# power.net
KiCad netlist of a schematic drawn in Altium Designer
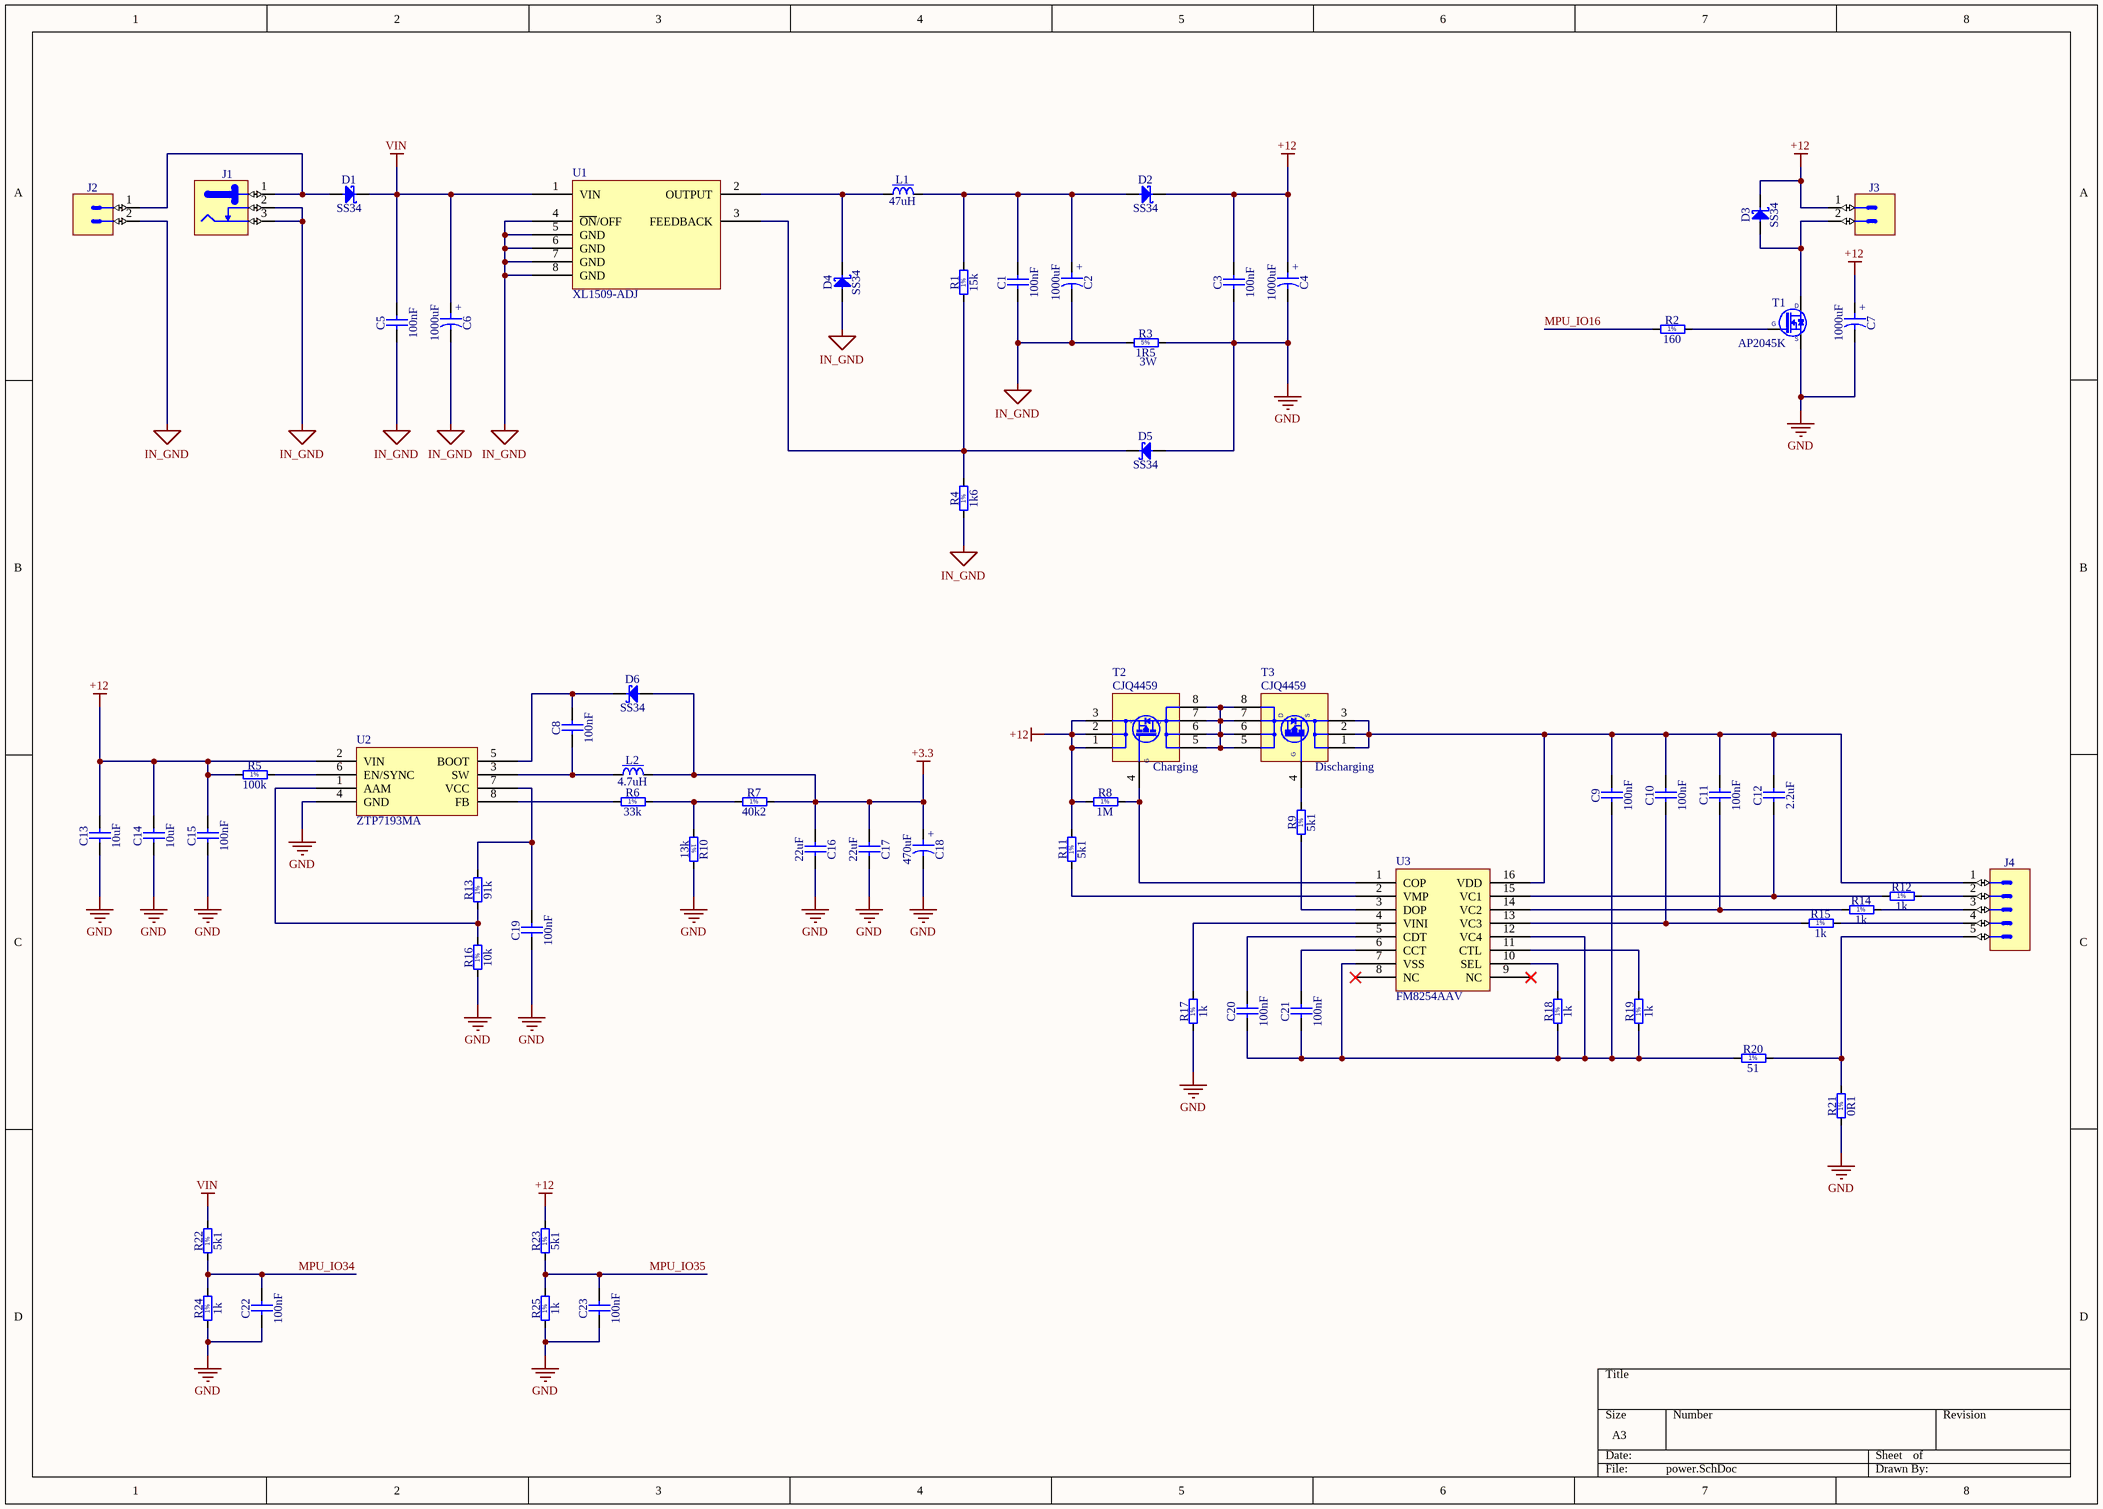
[diagram p0: power.SchDoc]

(export (version "E")
  (design (tool "Eeschema 10.0.6"))
  (components
    (comp (ref "C1")
      (value "100nF")
      (footprint "CAPC2012X135N")
      (description "Non-polarised capacitor")
      (fields
        (field (name "PART NUMBER") "CC0805_100NF_50V_10%_X7R")
        (field (name "VOLTAGE") "50V")
        (field (name "AUTHOR") "CERN DEM JLC")
      )
      (libsource (lib "Capacitors") (part "Capacitor - non polarized"))
    )
    (comp (ref "C2")
      (value "1000uF")
      (footprint "CAPPR500-1300X2200")
      (description "Polarised capacitor")
      (fields
        (field (name "PART NUMBER") "CAER_1000UF_25V_20%_RUBYCON_ZL")
        (field (name "VOLTAGE") "25V")
        (field (name "AUTHOR") "CERN DEM JLC")
      )
      (libsource (lib "Capacitors") (part "Capacitor - polarized"))
    )
    (comp (ref "C3")
      (value "100nF")
      (footprint "CAPC2012X135N")
      (description "Non-polarised capacitor")
      (fields
        (field (name "PART NUMBER") "CC0805_100NF_50V_10%_X7R")
        (field (name "VOLTAGE") "50V")
        (field (name "AUTHOR") "CERN DEM JLC")
      )
      (libsource (lib "Capacitors") (part "Capacitor - non polarized"))
    )
    (comp (ref "C4")
      (value "1000uF")
      (footprint "CAPPR500-1300X2200")
      (description "Polarised capacitor")
      (fields
        (field (name "PART NUMBER") "CAER_1000UF_25V_20%_RUBYCON_ZL")
        (field (name "VOLTAGE") "25V")
        (field (name "AUTHOR") "CERN DEM JLC")
      )
      (libsource (lib "Capacitors") (part "Capacitor - polarized"))
    )
    (comp (ref "C5")
      (value "100nF")
      (footprint "CAPC2012X135N")
      (description "Non-polarised capacitor")
      (fields
        (field (name "PART NUMBER") "CC0805_100NF_50V_10%_X7R")
        (field (name "VOLTAGE") "50V")
        (field (name "AUTHOR") "CERN DEM JLC")
      )
      (libsource (lib "Capacitors") (part "Capacitor - non polarized"))
    )
    (comp (ref "C6")
      (value "1000uF")
      (footprint "CAPPR500-1300X2200")
      (description "Polarised capacitor")
      (fields
        (field (name "PART NUMBER") "CAER_1000UF_25V_20%_RUBYCON_ZL")
        (field (name "VOLTAGE") "25V")
        (field (name "AUTHOR") "CERN DEM JLC")
      )
      (libsource (lib "Capacitors") (part "Capacitor - polarized"))
    )
    (comp (ref "C7")
      (value "1000uF")
      (footprint "CAPPR500-1300X2200")
      (description "Polarised capacitor")
      (fields
        (field (name "PART NUMBER") "CAER_1000UF_25V_20%_RUBYCON_ZL")
        (field (name "VOLTAGE") "25V")
        (field (name "AUTHOR") "CERN DEM JLC")
      )
      (libsource (lib "Capacitors") (part "Capacitor - polarized"))
    )
    (comp (ref "C8")
      (value "100nF")
      (footprint "CAPC2012X135N")
      (description "Non-polarised capacitor")
      (fields
        (field (name "PART NUMBER") "CC0805_100NF_50V_10%_X7R")
        (field (name "VOLTAGE") "50V")
        (field (name "AUTHOR") "CERN DEM JLC")
      )
      (libsource (lib "Capacitors") (part "Capacitor - non polarized"))
    )
    (comp (ref "C9")
      (value "100nF")
      (footprint "CAPC2012X135N")
      (description "Non-polarised capacitor")
      (fields
        (field (name "PART NUMBER") "CC0805_100NF_50V_10%_X7R")
        (field (name "VOLTAGE") "50V")
        (field (name "AUTHOR") "CERN DEM JLC")
      )
      (libsource (lib "Capacitors") (part "Capacitor - non polarized"))
    )
    (comp (ref "C10")
      (value "100nF")
      (footprint "CAPC2012X135N")
      (description "Non-polarised capacitor")
      (fields
        (field (name "PART NUMBER") "CC0805_100NF_50V_10%_X7R")
        (field (name "VOLTAGE") "50V")
        (field (name "AUTHOR") "CERN DEM JLC")
      )
      (libsource (lib "Capacitors") (part "Capacitor - non polarized"))
    )
    (comp (ref "C11")
      (value "100nF")
      (footprint "CAPC2012X135N")
      (description "Non-polarised capacitor")
      (fields
        (field (name "PART NUMBER") "CC0805_100NF_50V_10%_X7R")
        (field (name "VOLTAGE") "50V")
        (field (name "AUTHOR") "CERN DEM JLC")
      )
      (libsource (lib "Capacitors") (part "Capacitor - non polarized"))
    )
    (comp (ref "C12")
      (value "2.2uF")
      (footprint "CAPC2012X140N")
      (description "Non-polarised capacitor")
      (fields
        (field (name "PART NUMBER") "CC0805_2.2UF_50V_10%_X7R")
        (field (name "VOLTAGE") "50V")
        (field (name "AUTHOR") "CERN DEM JLC")
      )
      (libsource (lib "Capacitors") (part "Capacitor - non polarized"))
    )
    (comp (ref "C13")
      (value "10uF")
      (footprint "CAPC2012X135N")
      (description "Non-polarised capacitor")
      (fields
        (field (name "PART NUMBER") "CC0805_10UF_10V_10%_X7R")
        (field (name "VOLTAGE") "10V")
        (field (name "AUTHOR") "CERN DEM JLC")
      )
      (libsource (lib "Capacitors") (part "Capacitor - non polarized"))
    )
    (comp (ref "C14")
      (value "10uF")
      (footprint "CAPC2012X135N")
      (description "Non-polarised capacitor")
      (fields
        (field (name "PART NUMBER") "CC0805_10UF_10V_10%_X7R")
        (field (name "VOLTAGE") "10V")
        (field (name "AUTHOR") "CERN DEM JLC")
      )
      (libsource (lib "Capacitors") (part "Capacitor - non polarized"))
    )
    (comp (ref "C15")
      (value "100nF")
      (footprint "CAPC2012X135N")
      (description "Non-polarised capacitor")
      (fields
        (field (name "PART NUMBER") "CC0805_100NF_50V_10%_X7R")
        (field (name "VOLTAGE") "50V")
        (field (name "AUTHOR") "CERN DEM JLC")
      )
      (libsource (lib "Capacitors") (part "Capacitor - non polarized"))
    )
    (comp (ref "C16")
      (value "22uF")
      (footprint "CAPC2012X135N")
      (description "Non-polarised capacitor")
      (fields
        (field (name "PART NUMBER") "CC0805_22UF_6.3V_20%_X5R")
        (field (name "VOLTAGE") "6.3V")
        (field (name "AUTHOR") "CERN DEM JLC")
      )
      (libsource (lib "Capacitors") (part "Capacitor - non polarized"))
    )
    (comp (ref "C17")
      (value "22uF")
      (footprint "CAPC2012X135N")
      (description "Non-polarised capacitor")
      (fields
        (field (name "PART NUMBER") "CC0805_22UF_6.3V_20%_X5R")
        (field (name "VOLTAGE") "6.3V")
        (field (name "AUTHOR") "CERN DEM JLC")
      )
      (libsource (lib "Capacitors") (part "Capacitor - non polarized"))
    )
    (comp (ref "C18")
      (value "470uF")
      (footprint "CAPPR500-1050X1150")
      (description "Polarised capacitor")
      (fields
        (field (name "PART NUMBER") "CAER_470UF_10V_20%_500-1050X1150_LESR0R015")
        (field (name "VOLTAGE") "10V")
        (field (name "AUTHOR") "CERN DEM JLC")
      )
      (libsource (lib "Capacitors") (part "Capacitor - polarized"))
    )
    (comp (ref "C19")
      (value "100nF")
      (footprint "CAPC2012X135N")
      (description "Non-polarised capacitor")
      (fields
        (field (name "PART NUMBER") "CC0805_100NF_50V_10%_X7R")
        (field (name "VOLTAGE") "50V")
        (field (name "AUTHOR") "CERN DEM JLC")
      )
      (libsource (lib "Capacitors") (part "Capacitor - non polarized"))
    )
    (comp (ref "C20")
      (value "100nF")
      (footprint "CAPC2012X135N")
      (description "Non-polarised capacitor")
      (fields
        (field (name "PART NUMBER") "CC0805_100NF_50V_10%_X7R")
        (field (name "VOLTAGE") "50V")
        (field (name "AUTHOR") "CERN DEM JLC")
      )
      (libsource (lib "Capacitors") (part "Capacitor - non polarized"))
    )
    (comp (ref "C21")
      (value "100nF")
      (footprint "CAPC2012X135N")
      (description "Non-polarised capacitor")
      (fields
        (field (name "PART NUMBER") "CC0805_100NF_50V_10%_X7R")
        (field (name "VOLTAGE") "50V")
        (field (name "AUTHOR") "CERN DEM JLC")
      )
      (libsource (lib "Capacitors") (part "Capacitor - non polarized"))
    )
    (comp (ref "C22")
      (value "100nF")
      (footprint "CAPC2012X135N")
      (description "Non-polarised capacitor")
      (fields
        (field (name "PART NUMBER") "CC0805_100NF_50V_10%_X7R")
        (field (name "VOLTAGE") "50V")
        (field (name "AUTHOR") "CERN DEM JLC")
      )
      (libsource (lib "Capacitors") (part "Capacitor - non polarized"))
    )
    (comp (ref "C23")
      (value "100nF")
      (footprint "CAPC2012X135N")
      (description "Non-polarised capacitor")
      (fields
        (field (name "PART NUMBER") "CC0805_100NF_50V_10%_X7R")
        (field (name "VOLTAGE") "50V")
        (field (name "AUTHOR") "CERN DEM JLC")
      )
      (libsource (lib "Capacitors") (part "Capacitor - non polarized"))
    )
    (comp (ref "D1")
      (value "SS34")
      (footprint "DIOM5127X229N")
      (description "Schottky Diode")
      (fields
        (field (name "PART NUMBER") "SS16")
        (field (name "VOLTAGE") "60V")
        (field (name "AUTHOR") "CERN DEM JLC")
      )
      (libsource (lib "ICs And Semiconductors") (part "Diode Schottky"))
    )
    (comp (ref "D2")
      (value "SS34")
      (footprint "DIOM5127X229N")
      (description "Schottky Diode")
      (fields
        (field (name "PART NUMBER") "SS16")
        (field (name "VOLTAGE") "60V")
        (field (name "AUTHOR") "CERN DEM JLC")
      )
      (libsource (lib "ICs And Semiconductors") (part "Diode Schottky"))
    )
    (comp (ref "D3")
      (value "SS34")
      (footprint "DIOM5127X229N")
      (description "Schottky Diode")
      (fields
        (field (name "PART NUMBER") "SS16")
        (field (name "VOLTAGE") "60V")
        (field (name "AUTHOR") "CERN DEM JLC")
      )
      (libsource (lib "ICs And Semiconductors") (part "Diode Schottky"))
    )
    (comp (ref "D4")
      (value "SS34")
      (footprint "DIOM5127X229N")
      (description "Schottky Diode")
      (fields
        (field (name "PART NUMBER") "SS16")
        (field (name "VOLTAGE") "60V")
        (field (name "AUTHOR") "CERN DEM JLC")
      )
      (libsource (lib "ICs And Semiconductors") (part "Diode Schottky"))
    )
    (comp (ref "D5")
      (value "SS34")
      (footprint "DIOM5127X229N")
      (description "Schottky Diode")
      (fields
        (field (name "PART NUMBER") "SS16")
        (field (name "VOLTAGE") "60V")
        (field (name "AUTHOR") "CERN DEM JLC")
      )
      (libsource (lib "ICs And Semiconductors") (part "Diode Schottky"))
    )
    (comp (ref "D6")
      (value "SS34")
      (footprint "DIOM5127X229N")
      (description "Schottky Diode")
      (fields
        (field (name "PART NUMBER") "SS16")
        (field (name "VOLTAGE") "60V")
        (field (name "AUTHOR") "CERN DEM JLC")
      )
      (libsource (lib "ICs And Semiconductors") (part "Diode Schottky"))
    )
    (comp (ref "J1")
      (value "Jack")
      (footprint "CLIFF_FC68148(DC-10A)")
      (description "12V /  5A, 2.1mm Diameter Pin, DC Power Socket With  Switch. DC10A Type")
      (fields
        (field (name "PART NUMBER") "CLIFF_FC68148(DC-10A)")
        (field (name "MANUFACTURER") "CLIFF ELECTRONIC COMPONENTS")
        (field (name "AUTHOR") "CERN DEM JLC")
      )
      (libsource (lib "Connectors") (part "CLIFF_FC68148(DC-10A)"))
    )
    (comp (ref "J2")
      (value "Header 2")
      (footprint "WEIDMULLER_1146320000")
      (description "Connector 2 Male")
      (fields
        (field (name "PART NUMBER") "WEIDMULLER_1146320000")
        (field (name "MANUFACTURER") "WEIDMULLER")
        (field (name "AUTHOR") "CERN DEM JLC")
      )
      (libsource (lib "Connectors") (part "Connector 2 Male"))
    )
    (comp (ref "J3")
      (value "Header 2")
      (footprint "WEIDMULLER_1146320000")
      (description "Connector 2 Male")
      (fields
        (field (name "PART NUMBER") "WEIDMULLER_1146320000")
        (field (name "MANUFACTURER") "WEIDMULLER")
        (field (name "AUTHOR") "CERN DEM JLC")
      )
      (libsource (lib "") (part "Connector 2 Male_1"))
    )
    (comp (ref "J4")
      (value "Header 5")
      (footprint "WEIDMULLER_1146410000")
      (description "Connector 5 Male")
      (fields
        (field (name "PART NUMBER") "WEIDMULLER_1146410000")
        (field (name "MANUFACTURER") "WEIDMULLER")
        (field (name "AUTHOR") "CERN DEM JLC")
      )
      (libsource (lib "Connectors") (part "Connector 5 Male"))
    )
    (comp (ref "L1")
      (value "47uH")
      (footprint "IND_WURTH_WE-PD_XXL")
      (description "Inductor With Core")
      (fields
        (field (name "PART NUMBER") "IND_47UH_20%_WURTH_WE-PD_7447709470")
        (field (name "POWER") "3.8A")
        (field (name "AUTHOR") "CERN DEM JLC")
      )
      (libsource (lib "Inductors & Transformers") (part "Inductor With Magnetic core"))
    )
    (comp (ref "L2")
      (value "4.7uH")
      (footprint "IND_WURTH_WE-TPC-2813")
      (description "Inductor With Core")
      (fields
        (field (name "PART NUMBER") "IND_4.7UH_30%_WURTH_WE-TPC_744029004")
        (field (name "POWER") "1A")
        (field (name "AUTHOR") "CERN DEM JLC")
      )
      (libsource (lib "Inductors & Transformers") (part "Inductor With Magnetic core"))
    )
    (comp (ref "R1")
      (value "15k")
      (footprint "RESC2012X60N")
      (description "Resistor - 1%")
      (fields
        (field (name "PART NUMBER") "R0805_15K_1%_0.125W_100PPM")
        (field (name "POWER") "0.125W")
        (field (name "AUTHOR") "CERN DEM JLC")
      )
      (libsource (lib "Resistors") (part "Resistor - 1%"))
    )
    (comp (ref "R2")
      (value "160")
      (footprint "RESC2012X60N")
      (description "Resistor - 1%")
      (fields
        (field (name "PART NUMBER") "R0805_160R_1%_0.125W_100PPM")
        (field (name "POWER") "0.125W")
        (field (name "AUTHOR") "CERN DEM JLC")
      )
      (libsource (lib "Resistors") (part "Resistor - 1%"))
    )
    (comp (ref "R3")
      (value "1R5")
      (footprint "RES2286-1670X520")
      (description "Resistor - 5%")
      (fields
        (field (name "PART NUMBER") "RMF_1R8_5%_3W_250PPM_2286-1670X520")
        (field (name "POWER") "3W")
        (field (name "AUTHOR") "CERN DEM JLC")
      )
      (libsource (lib "Resistors") (part "Resistor - 5%"))
    )
    (comp (ref "R4")
      (value "1k6")
      (footprint "RESC2012X60N")
      (description "Resistor - 1%")
      (fields
        (field (name "PART NUMBER") "R0805_1K6_1%_0.125W_100PPM")
        (field (name "POWER") "0.125W")
        (field (name "AUTHOR") "CERN DEM JLC")
      )
      (libsource (lib "Resistors") (part "Resistor - 1%"))
    )
    (comp (ref "R5")
      (value "100k")
      (footprint "RESC2012X60N")
      (description "Resistor - 1%")
      (fields
        (field (name "PART NUMBER") "R0805_100K_1%_0.125W_100PPM")
        (field (name "POWER") "0.125W")
        (field (name "AUTHOR") "CERN DEM JLC")
      )
      (libsource (lib "Resistors") (part "Resistor - 1%"))
    )
    (comp (ref "R6")
      (value "33k")
      (footprint "RESC2012X60N")
      (description "Resistor - 1%")
      (fields
        (field (name "PART NUMBER") "R0805_33K_1%_0.125W_100PPM")
        (field (name "POWER") "0.125W")
        (field (name "AUTHOR") "CERN DEM JLC")
      )
      (libsource (lib "Resistors") (part "Resistor - 1%"))
    )
    (comp (ref "R7")
      (value "40k2")
      (footprint "RESC2012X60N")
      (description "Resistor - 1%")
      (fields
        (field (name "PART NUMBER") "R0805_40K2_1%_0.125W_100PPM")
        (field (name "POWER") "0.125W")
        (field (name "AUTHOR") "CERN DEM JLC")
      )
      (libsource (lib "Resistors") (part "Resistor - 1%"))
    )
    (comp (ref "R8")
      (value "1M")
      (footprint "RESC2012X60N")
      (description "Resistor - 1%")
      (fields
        (field (name "PART NUMBER") "R0805_1M_1%_0.125W_100PPM")
        (field (name "POWER") "0.125W")
        (field (name "AUTHOR") "CERN DEM JLC")
      )
      (libsource (lib "Resistors") (part "Resistor - 1%"))
    )
    (comp (ref "R9")
      (value "5k1")
      (footprint "RESC2012X60N")
      (description "Resistor - 1%")
      (fields
        (field (name "PART NUMBER") "R0805_5K1_1%_0.125W_100PPM")
        (field (name "POWER") "0.125W")
        (field (name "AUTHOR") "CERN DEM JLC")
      )
      (libsource (lib "Resistors") (part "Resistor - 1%"))
    )
    (comp (ref "R10")
      (value "13k")
      (footprint "RESC2012X60N")
      (description "Resistor - 1%")
      (fields
        (field (name "PART NUMBER") "R0805_13K_1%_0.125W_100PPM")
        (field (name "POWER") "0.125W")
        (field (name "AUTHOR") "CERN DEM JLC")
      )
      (libsource (lib "Resistors") (part "Resistor - 1%"))
    )
    (comp (ref "R11")
      (value "5k1")
      (footprint "RESC2012X60N")
      (description "Resistor - 1%")
      (fields
        (field (name "PART NUMBER") "R0805_5K1_1%_0.125W_100PPM")
        (field (name "POWER") "0.125W")
        (field (name "AUTHOR") "CERN DEM JLC")
      )
      (libsource (lib "Resistors") (part "Resistor - 1%"))
    )
    (comp (ref "R12")
      (value "1k")
      (footprint "RESC2012X60N")
      (description "Resistor - 1%")
      (fields
        (field (name "PART NUMBER") "R0805_1K_1%_0.125W_100PPM")
        (field (name "POWER") "0.125W")
        (field (name "AUTHOR") "CERN DEM JLC")
      )
      (libsource (lib "Resistors") (part "Resistor - 1%"))
    )
    (comp (ref "R13")
      (value "91k")
      (footprint "RESC2012X60N")
      (description "Resistor - 1%")
      (fields
        (field (name "PART NUMBER") "R0805_91K_1%_0.125W_100PPM")
        (field (name "POWER") "0.125W")
        (field (name "AUTHOR") "CERN DEM JLC")
      )
      (libsource (lib "Resistors") (part "Resistor - 1%"))
    )
    (comp (ref "R14")
      (value "1k")
      (footprint "RESC2012X60N")
      (description "Resistor - 1%")
      (fields
        (field (name "PART NUMBER") "R0805_1K_1%_0.125W_100PPM")
        (field (name "POWER") "0.125W")
        (field (name "AUTHOR") "CERN DEM JLC")
      )
      (libsource (lib "Resistors") (part "Resistor - 1%"))
    )
    (comp (ref "R15")
      (value "1k")
      (footprint "RESC2012X60N")
      (description "Resistor - 1%")
      (fields
        (field (name "PART NUMBER") "R0805_1K_1%_0.125W_100PPM")
        (field (name "POWER") "0.125W")
        (field (name "AUTHOR") "CERN DEM JLC")
      )
      (libsource (lib "Resistors") (part "Resistor - 1%"))
    )
    (comp (ref "R16")
      (value "10k")
      (footprint "RESC2012X60N")
      (description "Resistor - 1%")
      (fields
        (field (name "PART NUMBER") "R0805_10K_1%_0.125W_100PPM")
        (field (name "POWER") "0.125W")
        (field (name "AUTHOR") "CERN DEM JLC")
      )
      (libsource (lib "Resistors") (part "Resistor - 1%"))
    )
    (comp (ref "R17")
      (value "1k")
      (footprint "RESC2012X60N")
      (description "Resistor - 1%")
      (fields
        (field (name "PART NUMBER") "R0805_1K_1%_0.125W_100PPM")
        (field (name "POWER") "0.125W")
        (field (name "AUTHOR") "CERN DEM JLC")
      )
      (libsource (lib "Resistors") (part "Resistor - 1%"))
    )
    (comp (ref "R18")
      (value "1k")
      (footprint "RESC2012X60N")
      (description "Resistor - 1%")
      (fields
        (field (name "PART NUMBER") "R0805_1K_1%_0.125W_100PPM")
        (field (name "POWER") "0.125W")
        (field (name "AUTHOR") "CERN DEM JLC")
      )
      (libsource (lib "Resistors") (part "Resistor - 1%"))
    )
    (comp (ref "R19")
      (value "1k")
      (footprint "RESC2012X60N")
      (description "Resistor - 1%")
      (fields
        (field (name "PART NUMBER") "R0805_1K_1%_0.125W_100PPM")
        (field (name "POWER") "0.125W")
        (field (name "AUTHOR") "CERN DEM JLC")
      )
      (libsource (lib "Resistors") (part "Resistor - 1%"))
    )
    (comp (ref "R20")
      (value "51")
      (footprint "RESC2012X60N")
      (description "Resistor - 1%")
      (fields
        (field (name "PART NUMBER") "R0805_51R_1%_0.125W_100PPM")
        (field (name "POWER") "0.125W")
        (field (name "AUTHOR") "CERN DEM JLC")
      )
      (libsource (lib "Resistors") (part "Resistor - 1%"))
    )
    (comp (ref "R21")
      (value "0R1")
      (footprint "RESC6432X89N")
      (description "Resistor - 1%")
      (fields
        (field (name "PART NUMBER") "R2512_0R02_1%_1W_75PPM_VISHAY_WSL")
        (field (name "POWER") "1W")
        (field (name "AUTHOR") "CERN DEM JLC")
      )
      (libsource (lib "Resistors") (part "Resistor - 1%"))
    )
    (comp (ref "R22")
      (value "5k1")
      (footprint "RESC2012X60N")
      (description "Resistor - 1%")
      (fields
        (field (name "PART NUMBER") "R0805_5K1_1%_0.125W_100PPM")
        (field (name "POWER") "0.125W")
        (field (name "AUTHOR") "CERN DEM JLC")
      )
      (libsource (lib "Resistors") (part "Resistor - 1%"))
    )
    (comp (ref "R23")
      (value "5k1")
      (footprint "RESC2012X60N")
      (description "Resistor - 1%")
      (fields
        (field (name "PART NUMBER") "R0805_5K1_1%_0.125W_100PPM")
        (field (name "POWER") "0.125W")
        (field (name "AUTHOR") "CERN DEM JLC")
      )
      (libsource (lib "Resistors") (part "Resistor - 1%"))
    )
    (comp (ref "R24")
      (value "1k")
      (footprint "RESC2012X60N")
      (description "Resistor - 1%")
      (fields
        (field (name "PART NUMBER") "R0805_1K_1%_0.125W_100PPM")
        (field (name "POWER") "0.125W")
        (field (name "AUTHOR") "CERN DEM JLC")
      )
      (libsource (lib "Resistors") (part "Resistor - 1%"))
    )
    (comp (ref "R25")
      (value "1k")
      (footprint "RESC2012X60N")
      (description "Resistor - 1%")
      (fields
        (field (name "PART NUMBER") "R0805_1K_1%_0.125W_100PPM")
        (field (name "POWER") "0.125W")
        (field (name "AUTHOR") "CERN DEM JLC")
      )
      (libsource (lib "Resistors") (part "Resistor - 1%"))
    )
    (comp (ref "T1")
      (value "AP2045K")
      (footprint "TO228P991X239-3N-R552X520")
      (description "N-CHANNEL MOSFET WITH DIODE")
      (fields
        (field (name "PART NUMBER") "IPD600N25N3 G")
        (field (name "MANUFACTURER") "INFINEON")
        (field (name "AUTHOR") "CERN DEM JLC")
      )
      (libsource (lib "ICs And Semiconductors") (part "N-MOSFET-D 1G 2S 3D"))
    )
    (comp (ref "T2")
      (value "CJQ4459")
      (footprint "SOIC127P600X175-8N")
      (description "-30V -19.7A P-Channel MOSFET")
      (fields
        (field (name "PART NUMBER") "SI4425DDY-T1-GE3")
        (field (name "MANUFACTURER") "VISHAY SILICONIX")
        (field (name "AUTHOR") "CERN DEM MR")
      )
      (libsource (lib "") (part "SI4425DDY_1"))
    )
    (comp (ref "T3")
      (value "CJQ4459")
      (footprint "SOIC127P600X175-8N")
      (description "-30V -19.7A P-Channel MOSFET")
      (fields
        (field (name "PART NUMBER") "SI4425DDY-T1-GE3")
        (field (name "MANUFACTURER") "VISHAY SILICONIX")
        (field (name "AUTHOR") "CERN DEM MR")
      )
      (libsource (lib "ICs And Semiconductors") (part "SI4425DDY"))
    )
    (comp (ref "U1")
      (value "XL1509-ADJ")
      (footprint "PCB - LEADED - SOIC - TI SOIC-8 D:TI SOIC-8 D")
      (description "SOIC-8 DC-DC Converters ROHS")
      (libsource (lib "Schlib1") (part "XL1509-ADJ"))
    )
    (comp (ref "U2")
      (value "ZTP7193MA")
      (footprint "SOT-23-8:SOT-23-8")
      (description "-40℃~+125℃@(Ta) 1 Step-Down 0.8V~15V 4.5V~18V 3A 3μA 500kHz TSOT23-8 DC-DC Converters ROHS")
      (libsource (lib "ZTP7193MA") (part "ZTP7193MA"))
    )
    (comp (ref "U3")
      (value "FM8254AAV")
      (footprint "PCB - LEADED - SOP - TI TSSOP-16 PW:TI TSSOP-16 PW")
      (description "TSSOP-16 Battery Management ICs ROHS")
      (libsource (lib "FM8254AAV") (part "FM8254AAV"))
    )
  )
  (nets
    (net (code "1") (name "+3.3") (class "Default")
      (node (ref "C16") (pin "1") (pinfunction "1_1") (pintype "passive"))
      (node (ref "C17") (pin "1") (pinfunction "1_1") (pintype "passive"))
      (node (ref "C18") (pin "1") (pinfunction "1_1") (pintype "passive"))
      (node (ref "D6") (pin "2") (pinfunction "A_2") (pintype "passive"))
      (node (ref "L2") (pin "2") (pinfunction "2_2") (pintype "passive"))
      (node (ref "R7") (pin "2") (pinfunction "2_2") (pintype "passive"))
    )
    (net (code "2") (name "+12") (class "Default")
      (node (ref "C13") (pin "2") (pinfunction "2_2") (pintype "passive"))
      (node (ref "C14") (pin "2") (pinfunction "2_2") (pintype "passive"))
      (node (ref "C15") (pin "2") (pinfunction "2_2") (pintype "passive"))
      (node (ref "C3") (pin "2") (pinfunction "2_2") (pintype "passive"))
      (node (ref "C4") (pin "1") (pinfunction "1_1") (pintype "passive"))
      (node (ref "C7") (pin "1") (pinfunction "1_1") (pintype "passive"))
      (node (ref "D2") (pin "1") (pinfunction "C_1") (pintype "passive"))
      (node (ref "D3") (pin "1") (pinfunction "C_1") (pintype "passive"))
      (node (ref "J3") (pin "1") (pinfunction "1_1") (pintype "bidirectional"))
      (node (ref "R11") (pin "2") (pinfunction "2_2") (pintype "passive"))
      (node (ref "R23") (pin "2") (pinfunction "2_2") (pintype "passive"))
      (node (ref "R5") (pin "1") (pinfunction "1_1") (pintype "passive"))
      (node (ref "R8") (pin "1") (pinfunction "1_1") (pintype "passive"))
      (node (ref "T2") (pin "1") (pinfunction "S_1") (pintype "passive"))
      (node (ref "T2") (pin "2") (pinfunction "S_2") (pintype "passive"))
      (node (ref "T2") (pin "3") (pinfunction "S_3") (pintype "passive"))
      (node (ref "U2") (pin "2") (pinfunction "VIN_2") (pintype "passive"))
    )
    (net (code "3") (name "/MPU_IO16") (class "Default")
      (node (ref "R2") (pin "1") (pinfunction "1_1") (pintype "passive"))
    )
    (net (code "4") (name "/MPU_IO34") (class "Default")
      (node (ref "C22") (pin "2") (pinfunction "2_2") (pintype "passive"))
      (node (ref "R22") (pin "1") (pinfunction "1_1") (pintype "passive"))
      (node (ref "R24") (pin "2") (pinfunction "2_2") (pintype "passive"))
    )
    (net (code "5") (name "/MPU_IO35") (class "Default")
      (node (ref "C23") (pin "2") (pinfunction "2_2") (pintype "passive"))
      (node (ref "R23") (pin "1") (pinfunction "1_1") (pintype "passive"))
      (node (ref "R25") (pin "2") (pinfunction "2_2") (pintype "passive"))
    )
    (net (code "6") (name "GND") (class "Default")
      (node (ref "C13") (pin "1") (pinfunction "1_1") (pintype "passive"))
      (node (ref "C14") (pin "1") (pinfunction "1_1") (pintype "passive"))
      (node (ref "C15") (pin "1") (pinfunction "1_1") (pintype "passive"))
      (node (ref "C16") (pin "2") (pinfunction "2_2") (pintype "passive"))
      (node (ref "C17") (pin "2") (pinfunction "2_2") (pintype "passive"))
      (node (ref "C18") (pin "2") (pinfunction "2_2") (pintype "passive"))
      (node (ref "C19") (pin "1") (pinfunction "1_1") (pintype "passive"))
      (node (ref "C22") (pin "1") (pinfunction "1_1") (pintype "passive"))
      (node (ref "C23") (pin "1") (pinfunction "1_1") (pintype "passive"))
      (node (ref "C3") (pin "1") (pinfunction "1_1") (pintype "passive"))
      (node (ref "C4") (pin "2") (pinfunction "2_2") (pintype "passive"))
      (node (ref "C7") (pin "2") (pinfunction "2_2") (pintype "passive"))
      (node (ref "D5") (pin "2") (pinfunction "A_2") (pintype "passive"))
      (node (ref "R10") (pin "2") (pinfunction "2_2") (pintype "passive"))
      (node (ref "R16") (pin "1") (pinfunction "1_1") (pintype "passive"))
      (node (ref "R17") (pin "1") (pinfunction "1_1") (pintype "passive"))
      (node (ref "R21") (pin "1") (pinfunction "1_1") (pintype "passive"))
      (node (ref "R24") (pin "1") (pinfunction "1_1") (pintype "passive"))
      (node (ref "R25") (pin "1") (pinfunction "1_1") (pintype "passive"))
      (node (ref "R3") (pin "2") (pinfunction "2_2") (pintype "passive"))
      (node (ref "T1") (pin "2") (pinfunction "S_2") (pintype "passive"))
      (node (ref "U2") (pin "4") (pinfunction "GND_4") (pintype "passive"))
    )
    (net (code "7") (name "IN_GND") (class "Default")
      (node (ref "C1") (pin "1") (pinfunction "1_1") (pintype "passive"))
      (node (ref "C2") (pin "2") (pinfunction "2_2") (pintype "passive"))
      (node (ref "C5") (pin "1") (pinfunction "1_1") (pintype "passive"))
      (node (ref "C6") (pin "2") (pinfunction "2_2") (pintype "passive"))
      (node (ref "D4") (pin "2") (pinfunction "A_2") (pintype "passive"))
      (node (ref "J1") (pin "2") (pinfunction "2_2") (pintype "bidirectional"))
      (node (ref "J1") (pin "3") (pinfunction "3_3") (pintype "bidirectional"))
      (node (ref "J2") (pin "2") (pinfunction "2_2") (pintype "bidirectional"))
      (node (ref "R3") (pin "1") (pinfunction "1_1") (pintype "passive"))
      (node (ref "R4") (pin "1") (pinfunction "1_1") (pintype "passive"))
      (node (ref "U1") (pin "4") (pinfunction "~{ON}/OFF_4") (pintype "passive"))
      (node (ref "U1") (pin "5") (pinfunction "GND_5") (pintype "passive"))
      (node (ref "U1") (pin "6") (pinfunction "GND_6") (pintype "passive"))
      (node (ref "U1") (pin "7") (pinfunction "GND_7") (pintype "passive"))
      (node (ref "U1") (pin "8") (pinfunction "GND_8") (pintype "passive"))
    )
    (net (code "8") (name "Net-(D1-A)") (class "Default")
      (node (ref "D1") (pin "2") (pinfunction "A_2") (pintype "passive"))
      (node (ref "J1") (pin "1") (pinfunction "1_1") (pintype "bidirectional"))
      (node (ref "J2") (pin "1") (pinfunction "1_1") (pintype "bidirectional"))
    )
    (net (code "9") (name "Net-(D2-A)") (class "Default")
      (node (ref "C1") (pin "2") (pinfunction "2_2") (pintype "passive"))
      (node (ref "C2") (pin "1") (pinfunction "1_1") (pintype "passive"))
      (node (ref "D2") (pin "2") (pinfunction "A_2") (pintype "passive"))
      (node (ref "L1") (pin "2") (pinfunction "2_2") (pintype "passive"))
      (node (ref "R1") (pin "2") (pinfunction "2_2") (pintype "passive"))
    )
    (net (code "10") (name "Net-(D3-A)") (class "Default")
      (node (ref "D3") (pin "2") (pinfunction "A_2") (pintype "passive"))
      (node (ref "J3") (pin "2") (pinfunction "2_2") (pintype "bidirectional"))
      (node (ref "T1") (pin "3") (pinfunction "D_3") (pintype "passive"))
    )
    (net (code "11") (name "Net-(D4-C)") (class "Default")
      (node (ref "D4") (pin "1") (pinfunction "C_1") (pintype "passive"))
      (node (ref "L1") (pin "1") (pinfunction "1_1") (pintype "passive"))
      (node (ref "U1") (pin "2") (pinfunction "OUTPUT_2") (pintype "passive"))
    )
    (net (code "12") (name "Net-(D5-C)") (class "Default")
      (node (ref "D5") (pin "1") (pinfunction "C_1") (pintype "passive"))
      (node (ref "R1") (pin "1") (pinfunction "1_1") (pintype "passive"))
      (node (ref "R4") (pin "2") (pinfunction "2_2") (pintype "passive"))
      (node (ref "U1") (pin "3") (pinfunction "FEEDBACK_3") (pintype "passive"))
    )
    (net (code "13") (name "Net-(D6-C)") (class "Default")
      (node (ref "C8") (pin "2") (pinfunction "2_2") (pintype "passive"))
      (node (ref "D6") (pin "1") (pinfunction "C_1") (pintype "passive"))
      (node (ref "U2") (pin "5") (pinfunction "BOOT_5") (pintype "passive"))
    )
    (net (code "14") (name "Net-(J4-Pad2)") (class "Default")
      (node (ref "J4") (pin "2") (pinfunction "2_2") (pintype "bidirectional"))
      (node (ref "R12") (pin "2") (pinfunction "2_2") (pintype "passive"))
    )
    (net (code "15") (name "Net-(J4-Pad3)") (class "Default")
      (node (ref "J4") (pin "3") (pinfunction "3_3") (pintype "bidirectional"))
      (node (ref "R14") (pin "2") (pinfunction "2_2") (pintype "passive"))
    )
    (net (code "16") (name "Net-(J4-Pad4)") (class "Default")
      (node (ref "J4") (pin "4") (pinfunction "4_4") (pintype "bidirectional"))
      (node (ref "R15") (pin "2") (pinfunction "2_2") (pintype "passive"))
    )
    (net (code "17") (name "Net-(J4-Pad5)") (class "Default")
      (node (ref "J4") (pin "5") (pinfunction "5_5") (pintype "bidirectional"))
      (node (ref "R20") (pin "2") (pinfunction "2_2") (pintype "passive"))
      (node (ref "R21") (pin "2") (pinfunction "2_2") (pintype "passive"))
    )
    (net (code "18") (name "Net-(R9-Pad2)") (class "Default")
      (node (ref "R9") (pin "2") (pinfunction "2_2") (pintype "passive"))
      (node (ref "T3") (pin "4") (pinfunction "S_4") (pintype "passive"))
    )
    (net (code "19") (name "Net-(R10-Pad1)") (class "Default")
      (node (ref "R10") (pin "1") (pinfunction "1_1") (pintype "passive"))
      (node (ref "R6") (pin "2") (pinfunction "2_2") (pintype "passive"))
      (node (ref "R7") (pin "1") (pinfunction "1_1") (pintype "passive"))
    )
    (net (code "20") (name "Net-(T1-G)") (class "Default")
      (node (ref "R2") (pin "2") (pinfunction "2_2") (pintype "passive"))
      (node (ref "T1") (pin "1") (pinfunction "G_1") (pintype "passive"))
    )
    (net (code "21") (name "Net-(T2-D-Pad5)") (class "Default")
      (node (ref "T2") (pin "5") (pinfunction "D_5") (pintype "passive"))
      (node (ref "T2") (pin "6") (pinfunction "D_6") (pintype "passive"))
      (node (ref "T2") (pin "7") (pinfunction "D_7") (pintype "passive"))
      (node (ref "T2") (pin "8") (pinfunction "D_8") (pintype "passive"))
      (node (ref "T3") (pin "5") (pinfunction "D_5") (pintype "passive"))
      (node (ref "T3") (pin "6") (pinfunction "D_6") (pintype "passive"))
      (node (ref "T3") (pin "7") (pinfunction "D_7") (pintype "passive"))
      (node (ref "T3") (pin "8") (pinfunction "D_8") (pintype "passive"))
    )
    (net (code "22") (name "Net-(U2-AAM)") (class "Default")
      (node (ref "R13") (pin "1") (pinfunction "1_1") (pintype "passive"))
      (node (ref "R16") (pin "2") (pinfunction "2_2") (pintype "passive"))
      (node (ref "U2") (pin "1") (pinfunction "AAM_1") (pintype "passive"))
    )
    (net (code "23") (name "Net-(U2-EN{slash}SYNC)") (class "Default")
      (node (ref "R5") (pin "2") (pinfunction "2_2") (pintype "passive"))
      (node (ref "U2") (pin "6") (pinfunction "EN/SYNC_6") (pintype "passive"))
    )
    (net (code "24") (name "Net-(U2-FB)") (class "Default")
      (node (ref "R6") (pin "1") (pinfunction "1_1") (pintype "passive"))
      (node (ref "U2") (pin "8") (pinfunction "FB_8") (pintype "passive"))
    )
    (net (code "25") (name "Net-(U2-SW)") (class "Default")
      (node (ref "C8") (pin "1") (pinfunction "1_1") (pintype "passive"))
      (node (ref "L2") (pin "1") (pinfunction "1_1") (pintype "passive"))
      (node (ref "U2") (pin "3") (pinfunction "SW_3") (pintype "passive"))
    )
    (net (code "26") (name "Net-(U2-VCC)") (class "Default")
      (node (ref "C19") (pin "2") (pinfunction "2_2") (pintype "passive"))
      (node (ref "R13") (pin "2") (pinfunction "2_2") (pintype "passive"))
      (node (ref "U2") (pin "7") (pinfunction "VCC_7") (pintype "passive"))
    )
    (net (code "27") (name "Net-(U3-CCT)") (class "Default")
      (node (ref "C21") (pin "2") (pinfunction "2_2") (pintype "passive"))
      (node (ref "U3") (pin "6") (pinfunction "CCT_6") (pintype "passive"))
    )
    (net (code "28") (name "Net-(U3-CDT)") (class "Default")
      (node (ref "C20") (pin "2") (pinfunction "2_2") (pintype "passive"))
      (node (ref "U3") (pin "5") (pinfunction "CDT_5") (pintype "passive"))
    )
    (net (code "29") (name "Net-(U3-COP)") (class "Default")
      (node (ref "R8") (pin "2") (pinfunction "2_2") (pintype "passive"))
      (node (ref "T2") (pin "4") (pinfunction "S_4") (pintype "passive"))
      (node (ref "U3") (pin "1") (pinfunction "COP_1") (pintype "passive"))
    )
    (net (code "30") (name "Net-(U3-CTL)") (class "Default")
      (node (ref "R19") (pin "2") (pinfunction "2_2") (pintype "passive"))
      (node (ref "U3") (pin "11") (pinfunction "CTL_11") (pintype "passive"))
    )
    (net (code "31") (name "Net-(U3-DOP)") (class "Default")
      (node (ref "R9") (pin "1") (pinfunction "1_1") (pintype "passive"))
      (node (ref "U3") (pin "3") (pinfunction "DOP_3") (pintype "passive"))
    )
    (net (code "32") (name "Net-(U3-SEL)") (class "Default")
      (node (ref "R18") (pin "2") (pinfunction "2_2") (pintype "passive"))
      (node (ref "U3") (pin "10") (pinfunction "SEL_10") (pintype "passive"))
    )
    (net (code "33") (name "Net-(U3-VC1)") (class "Default")
      (node (ref "C12") (pin "1") (pinfunction "1_1") (pintype "passive"))
      (node (ref "R12") (pin "1") (pinfunction "1_1") (pintype "passive"))
      (node (ref "U3") (pin "15") (pinfunction "VC1_15") (pintype "passive"))
    )
    (net (code "34") (name "Net-(U3-VC2)") (class "Default")
      (node (ref "C11") (pin "1") (pinfunction "1_1") (pintype "passive"))
      (node (ref "R14") (pin "1") (pinfunction "1_1") (pintype "passive"))
      (node (ref "U3") (pin "14") (pinfunction "VC2_14") (pintype "passive"))
    )
    (net (code "35") (name "Net-(U3-VC3)") (class "Default")
      (node (ref "C10") (pin "1") (pinfunction "1_1") (pintype "passive"))
      (node (ref "R15") (pin "1") (pinfunction "1_1") (pintype "passive"))
      (node (ref "U3") (pin "13") (pinfunction "VC3_13") (pintype "passive"))
    )
    (net (code "36") (name "Net-(U3-VC4)") (class "Default")
      (node (ref "C20") (pin "1") (pinfunction "1_1") (pintype "passive"))
      (node (ref "C21") (pin "1") (pinfunction "1_1") (pintype "passive"))
      (node (ref "C9") (pin "1") (pinfunction "1_1") (pintype "passive"))
      (node (ref "R18") (pin "1") (pinfunction "1_1") (pintype "passive"))
      (node (ref "R19") (pin "1") (pinfunction "1_1") (pintype "passive"))
      (node (ref "R20") (pin "1") (pinfunction "1_1") (pintype "passive"))
      (node (ref "U3") (pin "12") (pinfunction "VC4_12") (pintype "passive"))
      (node (ref "U3") (pin "7") (pinfunction "VSS_7") (pintype "passive"))
    )
    (net (code "37") (name "Net-(U3-VDD)") (class "Default")
      (node (ref "C10") (pin "2") (pinfunction "2_2") (pintype "passive"))
      (node (ref "C11") (pin "2") (pinfunction "2_2") (pintype "passive"))
      (node (ref "C12") (pin "2") (pinfunction "2_2") (pintype "passive"))
      (node (ref "C9") (pin "2") (pinfunction "2_2") (pintype "passive"))
      (node (ref "J4") (pin "1") (pinfunction "1_1") (pintype "bidirectional"))
      (node (ref "T3") (pin "1") (pinfunction "S_1") (pintype "passive"))
      (node (ref "T3") (pin "2") (pinfunction "S_2") (pintype "passive"))
      (node (ref "T3") (pin "3") (pinfunction "S_3") (pintype "passive"))
      (node (ref "U3") (pin "16") (pinfunction "VDD_16") (pintype "passive"))
    )
    (net (code "38") (name "Net-(U3-VINI)") (class "Default")
      (node (ref "R17") (pin "2") (pinfunction "2_2") (pintype "passive"))
      (node (ref "U3") (pin "4") (pinfunction "VINI_4") (pintype "passive"))
    )
    (net (code "39") (name "Net-(U3-VMP)") (class "Default")
      (node (ref "R11") (pin "1") (pinfunction "1_1") (pintype "passive"))
      (node (ref "U3") (pin "2") (pinfunction "VMP_2") (pintype "passive"))
    )
    (net (code "40") (name "VIN") (class "Default")
      (node (ref "C5") (pin "2") (pinfunction "2_2") (pintype "passive"))
      (node (ref "C6") (pin "1") (pinfunction "1_1") (pintype "passive"))
      (node (ref "D1") (pin "1") (pinfunction "C_1") (pintype "passive"))
      (node (ref "R22") (pin "2") (pinfunction "2_2") (pintype "passive"))
      (node (ref "U1") (pin "1") (pinfunction "VIN_1") (pintype "passive"))
    )
    (net (code "41") (name "unconnected-(U3-NC-Pad8)") (class "Default")
      (node (ref "U3") (pin "8") (pinfunction "NC_8") (pintype "passive+no_connect"))
    )
    (net (code "42") (name "unconnected-(U3-NC-Pad9)") (class "Default")
      (node (ref "U3") (pin "9") (pinfunction "NC_9") (pintype "passive+no_connect"))
    )
  )
)
